# SCH_Claysight-MK1.net
KiCad netlist of a schematic drawn in EasyEDA
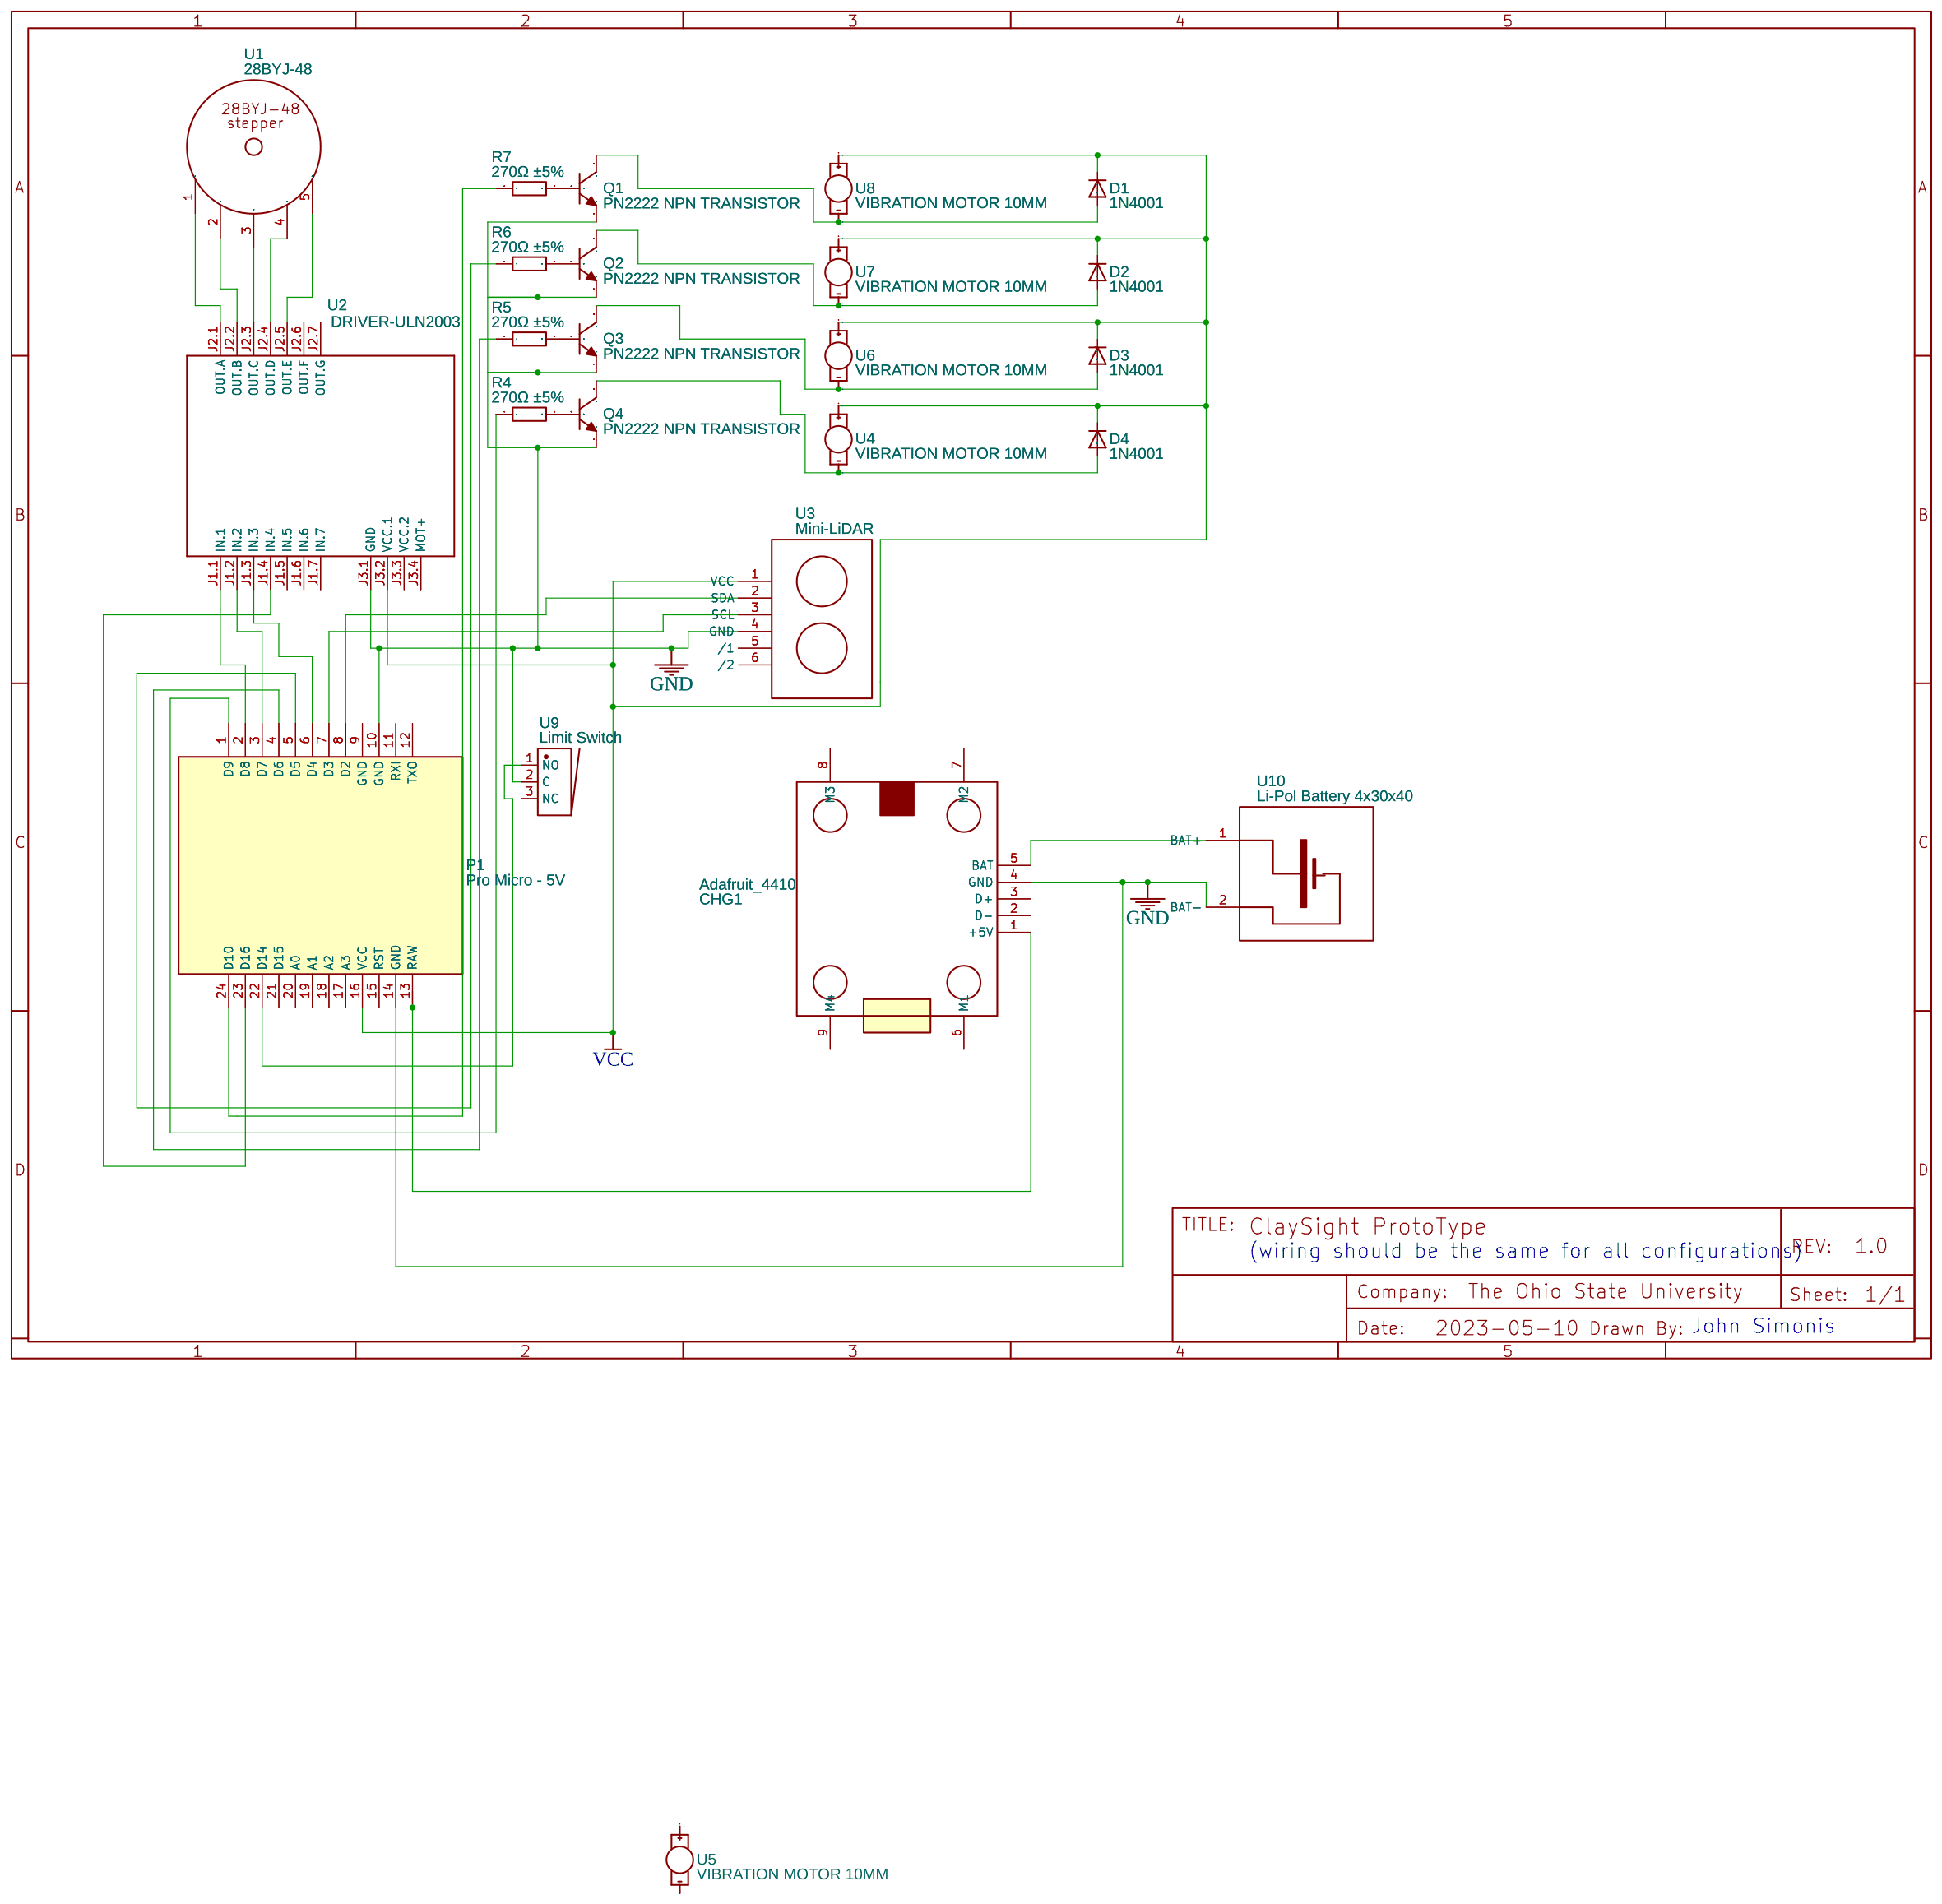
[diagram p0: schematic sheet]

(export (version "E")
  (design (tool "Eeschema 10.0.6"))
  (components
    (comp (ref "CHG1")
      (value "Adafruit_4410")
      (fields (field (name "BOM_Manufacturer Part") "4410") (field (name "BOM_Supplier Part") "1528-4410-ND"))
      (libsource (lib "") (part "Adafruit_4410"))
    )
    (comp (ref "D1") (value "1N4001") (libsource (lib "") (part "1N4001")))
    (comp (ref "D2") (value "1N4001") (libsource (lib "") (part "1N4001")))
    (comp (ref "D3") (value "1N4001") (libsource (lib "") (part "1N4001")))
    (comp (ref "D4") (value "1N4001") (libsource (lib "") (part "1N4001")))
    (comp (ref "P1") (value "Pro Micro - 5V") (libsource (lib "") (part "Pro Micro - 5V")))
    (comp (ref "Q1")
      (value "PN2222 NPN TRANSISTOR")
      (fields (field (name "BOM_Manufacturer Part") "2N3904") (field (name "BOM_Supplier Part") "C713605"))
      (libsource (lib "") (part "PN2222 NPN TRANSISTOR"))
    )
    (comp (ref "Q2")
      (value "PN2222 NPN TRANSISTOR")
      (fields (field (name "BOM_Manufacturer Part") "2N3904") (field (name "BOM_Supplier Part") "C713605"))
      (libsource (lib "") (part "PN2222 NPN TRANSISTOR"))
    )
    (comp (ref "Q3")
      (value "PN2222 NPN TRANSISTOR")
      (fields (field (name "BOM_Manufacturer Part") "2N3904") (field (name "BOM_Supplier Part") "C713605"))
      (libsource (lib "") (part "PN2222 NPN TRANSISTOR"))
    )
    (comp (ref "Q4")
      (value "PN2222 NPN TRANSISTOR")
      (fields (field (name "BOM_Manufacturer Part") "2N3904") (field (name "BOM_Supplier Part") "C713605"))
      (libsource (lib "") (part "PN2222 NPN TRANSISTOR"))
    )
    (comp (ref "R4")
      (value "270Ω ±5%")
      (fields
        (field (name "BOM_Manufacturer Part") "270Ω ±5% 20W")
        (field (name "BOM_Supplier Part") "undefined")
      )
      (libsource (lib "") (part "270Ω ±5% 20W"))
    )
    (comp (ref "R5")
      (value "270Ω ±5%")
      (fields
        (field (name "BOM_Manufacturer Part") "270Ω ±5% 20W")
        (field (name "BOM_Supplier Part") "undefined")
      )
      (libsource (lib "") (part "270Ω ±5% 20W"))
    )
    (comp (ref "R6")
      (value "270Ω ±5%")
      (fields
        (field (name "BOM_Manufacturer Part") "270Ω ±5% 20W")
        (field (name "BOM_Supplier Part") "undefined")
      )
      (libsource (lib "") (part "270Ω ±5% 20W"))
    )
    (comp (ref "R7")
      (value "270Ω ±5%")
      (fields
        (field (name "BOM_Manufacturer Part") "270Ω ±5% 20W")
        (field (name "BOM_Supplier Part") "undefined")
      )
      (libsource (lib "") (part "270Ω ±5% 20W"))
    )
    (comp (ref "U1") (value "28BYJ-48") (libsource (lib "") (part "28BYJ-48")))
    (comp (ref "U2") (value "DRIVER-ULN2003") (libsource (lib "") (part "DRIVER-ULN2003")))
    (comp (ref "U3") (value "Mini-LiDAR") (libsource (lib "") (part "TF Luna LiDAR")))
    (comp (ref "U4") (value "VIBRATION MOTOR 10MM") (libsource (lib "") (part "VIBRATION MOTOR 10MM")))
    (comp (ref "U5") (value "VIBRATION MOTOR 10MM") (libsource (lib "") (part "VIBRATION MOTOR 10MM")))
    (comp (ref "U6") (value "VIBRATION MOTOR 10MM") (libsource (lib "") (part "VIBRATION MOTOR 10MM")))
    (comp (ref "U7") (value "VIBRATION MOTOR 10MM") (libsource (lib "") (part "VIBRATION MOTOR 10MM")))
    (comp (ref "U8") (value "VIBRATION MOTOR 10MM") (libsource (lib "") (part "VIBRATION MOTOR 10MM")))
    (comp (ref "U9") (value "Limit Switch") (libsource (lib "") (part "Limit Switch")))
    (comp (ref "U10")
      (value "Li-Pol Battery 4x30x40")
      (fields (field (name "BOM_Manufacturer Part") "540-563"))
      (libsource (lib "") (part "Li-Pol Battery 4x30x40"))
    )
  )
  (nets
    (net (code "1") (name "GND") (class "Default")
      (node (ref "CHG1") (pin "4") (pinfunction "GND_4") (pintype "unspecified"))
      (node (ref "P1") (pin "10") (pinfunction "GND_10") (pintype "unspecified"))
      (node (ref "P1") (pin "14") (pinfunction "GND_14") (pintype "unspecified"))
      (node (ref "Q1") (pin "1") (pinfunction "E_1") (pintype "unspecified"))
      (node (ref "Q2") (pin "1") (pinfunction "E_1") (pintype "unspecified"))
      (node (ref "Q3") (pin "1") (pinfunction "E_1") (pintype "unspecified"))
      (node (ref "Q4") (pin "1") (pinfunction "E_1") (pintype "unspecified"))
      (node (ref "U2") (pin "J3.1") (pinfunction "GND_J3.1") (pintype "passive"))
      (node (ref "U9") (pin "2") (pinfunction "C_2") (pintype "unspecified"))
    )
    (net (code "2") (name "Net-(CHG1-+5V)") (class "Default")
      (node (ref "CHG1") (pin "1") (pinfunction "+5V_1") (pintype "unspecified"))
      (node (ref "P1") (pin "13") (pinfunction "RAW_13") (pintype "unspecified"))
    )
    (net (code "3") (name "Net-(P1-D4)") (class "Default")
      (node (ref "P1") (pin "6") (pinfunction "D4_6") (pintype "unspecified"))
      (node (ref "U2") (pin "J1.3") (pinfunction "IN.3_J1.3") (pintype "unspecified"))
    )
    (net (code "4") (name "Net-(P1-D5)") (class "Default")
      (node (ref "P1") (pin "5") (pinfunction "D5_5") (pintype "unspecified"))
      (node (ref "R6") (pin "1") (pinfunction "1_1") (pintype "input"))
    )
    (net (code "5") (name "Net-(P1-D6)") (class "Default")
      (node (ref "P1") (pin "4") (pinfunction "D6_4") (pintype "unspecified"))
      (node (ref "R5") (pin "1") (pinfunction "1_1") (pintype "input"))
    )
    (net (code "6") (name "Net-(P1-D7)") (class "Default")
      (node (ref "P1") (pin "3") (pinfunction "D7_3") (pintype "unspecified"))
      (node (ref "U2") (pin "J1.2") (pinfunction "IN.2_J1.2") (pintype "unspecified"))
    )
    (net (code "7") (name "Net-(P1-D8)") (class "Default")
      (node (ref "P1") (pin "2") (pinfunction "D8_2") (pintype "unspecified"))
      (node (ref "U2") (pin "J1.1") (pinfunction "IN.1_J1.1") (pintype "unspecified"))
    )
    (net (code "8") (name "Net-(P1-D9)") (class "Default")
      (node (ref "P1") (pin "1") (pinfunction "D9_1") (pintype "unspecified"))
      (node (ref "R4") (pin "1") (pinfunction "1_1") (pintype "input"))
    )
    (net (code "9") (name "Net-(P1-D10)") (class "Default")
      (node (ref "P1") (pin "24") (pinfunction "D10_24") (pintype "unspecified"))
      (node (ref "R7") (pin "1") (pinfunction "1_1") (pintype "input"))
    )
    (net (code "10") (name "Net-(P1-D14)") (class "Default")
      (node (ref "P1") (pin "22") (pinfunction "D14_22") (pintype "unspecified"))
      (node (ref "U9") (pin "1") (pinfunction "NO_1") (pintype "unspecified"))
    )
    (net (code "11") (name "Net-(P1-D16)") (class "Default")
      (node (ref "P1") (pin "23") (pinfunction "D16_23") (pintype "unspecified"))
      (node (ref "U2") (pin "J1.4") (pinfunction "IN.4_J1.4") (pintype "unspecified"))
    )
    (net (code "12") (name "Net-(Q1-B)") (class "Default")
      (node (ref "Q1") (pin "2") (pinfunction "B_2") (pintype "unspecified"))
      (node (ref "R7") (pin "2") (pinfunction "2_2") (pintype "input"))
    )
    (net (code "13") (name "Net-(Q1-C)") (class "Default")
      (node (ref "D1") (pin "A") (pinfunction "A_A") (pintype "unspecified"))
      (node (ref "Q1") (pin "3") (pinfunction "C_3") (pintype "unspecified"))
      (node (ref "U8") (pin "-") (pinfunction "-_-") (pintype "unspecified"))
    )
    (net (code "14") (name "Net-(Q2-B)") (class "Default")
      (node (ref "Q2") (pin "2") (pinfunction "B_2") (pintype "unspecified"))
      (node (ref "R6") (pin "2") (pinfunction "2_2") (pintype "input"))
    )
    (net (code "15") (name "Net-(Q2-C)") (class "Default")
      (node (ref "D2") (pin "A") (pinfunction "A_A") (pintype "unspecified"))
      (node (ref "Q2") (pin "3") (pinfunction "C_3") (pintype "unspecified"))
      (node (ref "U7") (pin "-") (pinfunction "-_-") (pintype "unspecified"))
    )
    (net (code "16") (name "Net-(Q3-B)") (class "Default")
      (node (ref "Q3") (pin "2") (pinfunction "B_2") (pintype "unspecified"))
      (node (ref "R5") (pin "2") (pinfunction "2_2") (pintype "input"))
    )
    (net (code "17") (name "Net-(Q3-C)") (class "Default")
      (node (ref "D3") (pin "A") (pinfunction "A_A") (pintype "unspecified"))
      (node (ref "Q3") (pin "3") (pinfunction "C_3") (pintype "unspecified"))
      (node (ref "U6") (pin "-") (pinfunction "-_-") (pintype "unspecified"))
    )
    (net (code "18") (name "Net-(Q4-B)") (class "Default")
      (node (ref "Q4") (pin "2") (pinfunction "B_2") (pintype "unspecified"))
      (node (ref "R4") (pin "2") (pinfunction "2_2") (pintype "input"))
    )
    (net (code "19") (name "Net-(Q4-C)") (class "Default")
      (node (ref "D4") (pin "A") (pinfunction "A_A") (pintype "unspecified"))
      (node (ref "Q4") (pin "3") (pinfunction "C_3") (pintype "unspecified"))
      (node (ref "U4") (pin "-") (pinfunction "-_-") (pintype "unspecified"))
    )
    (net (code "20") (name "Net-(U2-OUT.A)") (class "Default")
      (node (ref "U1") (pin "1") (pinfunction "1_1") (pintype "unspecified"))
      (node (ref "U2") (pin "J2.1") (pinfunction "OUT.A_J2.1") (pintype "unspecified"))
    )
    (net (code "21") (name "Net-(U2-OUT.B)") (class "Default")
      (node (ref "U1") (pin "2") (pinfunction "2_2") (pintype "unspecified"))
      (node (ref "U2") (pin "J2.2") (pinfunction "OUT.B_J2.2") (pintype "unspecified"))
    )
    (net (code "22") (name "Net-(U2-OUT.C)") (class "Default")
      (node (ref "U1") (pin "3") (pinfunction "3_3") (pintype "unspecified"))
      (node (ref "U2") (pin "J2.3") (pinfunction "OUT.C_J2.3") (pintype "unspecified"))
    )
    (net (code "23") (name "Net-(U2-OUT.D)") (class "Default")
      (node (ref "U1") (pin "4") (pinfunction "4_4") (pintype "unspecified"))
      (node (ref "U2") (pin "J2.4") (pinfunction "OUT.D_J2.4") (pintype "unspecified"))
    )
    (net (code "24") (name "Net-(U2-OUT.E)") (class "Default")
      (node (ref "U1") (pin "5") (pinfunction "5_5") (pintype "unspecified"))
      (node (ref "U2") (pin "J2.5") (pinfunction "OUT.E_J2.5") (pintype "unspecified"))
    )
    (net (code "25") (name "VCC") (class "Default")
      (node (ref "D1") (pin "C") (pinfunction "C_C") (pintype "unspecified"))
      (node (ref "D2") (pin "C") (pinfunction "C_C") (pintype "unspecified"))
      (node (ref "D3") (pin "C") (pinfunction "C_C") (pintype "unspecified"))
      (node (ref "D4") (pin "C") (pinfunction "C_C") (pintype "unspecified"))
      (node (ref "P1") (pin "16") (pinfunction "VCC_16") (pintype "unspecified"))
      (node (ref "U2") (pin "J3.2") (pinfunction "VCC.1_J3.2") (pintype "passive"))
      (node (ref "U4") (pin "+") (pinfunction "+_+") (pintype "unspecified"))
      (node (ref "U6") (pin "+") (pinfunction "+_+") (pintype "unspecified"))
      (node (ref "U7") (pin "+") (pinfunction "+_+") (pintype "unspecified"))
      (node (ref "U8") (pin "+") (pinfunction "+_+") (pintype "unspecified"))
    )
    (net (code "26") (name "unconnected-(CHG1-BAT-Pad5)") (class "Default")
      (node (ref "CHG1") (pin "5") (pinfunction "BAT_5") (pintype "unspecified"))
    )
    (net (code "27") (name "unconnected-(CHG1-D+-Pad3)") (class "Default")
      (node (ref "CHG1") (pin "3") (pinfunction "D+_3") (pintype "unspecified"))
    )
    (net (code "28") (name "unconnected-(CHG1-D--Pad2)") (class "Default")
      (node (ref "CHG1") (pin "2") (pinfunction "D-_2") (pintype "unspecified"))
    )
    (net (code "29") (name "unconnected-(CHG1-M1-Pad6)") (class "Default")
      (node (ref "CHG1") (pin "6") (pinfunction "M1_6") (pintype "unspecified"))
    )
    (net (code "30") (name "unconnected-(CHG1-M2-Pad7)") (class "Default")
      (node (ref "CHG1") (pin "7") (pinfunction "M2_7") (pintype "unspecified"))
    )
    (net (code "31") (name "unconnected-(CHG1-M3-Pad8)") (class "Default")
      (node (ref "CHG1") (pin "8") (pinfunction "M3_8") (pintype "unspecified"))
    )
    (net (code "32") (name "unconnected-(CHG1-M4-Pad9)") (class "Default")
      (node (ref "CHG1") (pin "9") (pinfunction "M4_9") (pintype "unspecified"))
    )
    (net (code "33") (name "unconnected-(P1-A0-Pad20)") (class "Default")
      (node (ref "P1") (pin "20") (pinfunction "A0_20") (pintype "unspecified"))
    )
    (net (code "34") (name "unconnected-(P1-A1-Pad19)") (class "Default")
      (node (ref "P1") (pin "19") (pinfunction "A1_19") (pintype "unspecified"))
    )
    (net (code "35") (name "unconnected-(P1-A2-Pad18)") (class "Default")
      (node (ref "P1") (pin "18") (pinfunction "A2_18") (pintype "unspecified"))
    )
    (net (code "36") (name "unconnected-(P1-A3-Pad17)") (class "Default")
      (node (ref "P1") (pin "17") (pinfunction "A3_17") (pintype "unspecified"))
    )
    (net (code "37") (name "unconnected-(P1-D2-Pad8)") (class "Default")
      (node (ref "P1") (pin "8") (pinfunction "D2_8") (pintype "unspecified"))
    )
    (net (code "38") (name "unconnected-(P1-D3-Pad7)") (class "Default")
      (node (ref "P1") (pin "7") (pinfunction "D3_7") (pintype "unspecified"))
    )
    (net (code "39") (name "unconnected-(P1-D15-Pad21)") (class "Default")
      (node (ref "P1") (pin "21") (pinfunction "D15_21") (pintype "unspecified"))
    )
    (net (code "40") (name "unconnected-(P1-GND-Pad9)") (class "Default")
      (node (ref "P1") (pin "9") (pinfunction "GND_9") (pintype "unspecified"))
    )
    (net (code "41") (name "unconnected-(P1-RST-Pad15)") (class "Default")
      (node (ref "P1") (pin "15") (pinfunction "RST_15") (pintype "unspecified"))
    )
    (net (code "42") (name "unconnected-(P1-RXI-Pad11)") (class "Default")
      (node (ref "P1") (pin "11") (pinfunction "RXI_11") (pintype "unspecified"))
    )
    (net (code "43") (name "unconnected-(P1-TXO-Pad12)") (class "Default")
      (node (ref "P1") (pin "12") (pinfunction "TXO_12") (pintype "unspecified"))
    )
    (net (code "44") (name "unconnected-(U2-IN.5-PadJ1.5)") (class "Default")
      (node (ref "U2") (pin "J1.5") (pinfunction "IN.5_J1.5") (pintype "unspecified"))
    )
    (net (code "45") (name "unconnected-(U2-IN.6-PadJ1.6)") (class "Default")
      (node (ref "U2") (pin "J1.6") (pinfunction "IN.6_J1.6") (pintype "unspecified"))
    )
    (net (code "46") (name "unconnected-(U2-IN.7-PadJ1.7)") (class "Default")
      (node (ref "U2") (pin "J1.7") (pinfunction "IN.7_J1.7") (pintype "unspecified"))
    )
    (net (code "47") (name "unconnected-(U2-MOT+-PadJ3.4)") (class "Default")
      (node (ref "U2") (pin "J3.4") (pinfunction "MOT+_J3.4") (pintype "unspecified"))
    )
    (net (code "48") (name "unconnected-(U2-OUT.F-PadJ2.6)") (class "Default")
      (node (ref "U2") (pin "J2.6") (pinfunction "OUT.F_J2.6") (pintype "unspecified"))
    )
    (net (code "49") (name "unconnected-(U2-OUT.G-PadJ2.7)") (class "Default")
      (node (ref "U2") (pin "J2.7") (pinfunction "OUT.G_J2.7") (pintype "unspecified"))
    )
    (net (code "50") (name "unconnected-(U2-VCC.2-PadJ3.3)") (class "Default")
      (node (ref "U2") (pin "J3.3") (pinfunction "VCC.2_J3.3") (pintype "unspecified"))
    )
    (net (code "51") (name "unconnected-(U3-GND-Pad4)") (class "Default")
      (node (ref "U3") (pin "4") (pinfunction "GND_4") (pintype "unspecified"))
    )
    (net (code "52") (name "unconnected-(U3-SCL-Pad3)") (class "Default")
      (node (ref "U3") (pin "3") (pinfunction "SCL_3") (pintype "unspecified"))
    )
    (net (code "53") (name "unconnected-(U3-SDA-Pad2)") (class "Default")
      (node (ref "U3") (pin "2") (pinfunction "SDA_2") (pintype "unspecified"))
    )
    (net (code "54") (name "unconnected-(U3-VCC-Pad1)") (class "Default")
      (node (ref "U3") (pin "1") (pinfunction "VCC_1") (pintype "unspecified"))
    )
    (net (code "55") (name "unconnected-(U3-{slash}1-Pad5)") (class "Default")
      (node (ref "U3") (pin "5") (pinfunction "/1_5") (pintype "unspecified"))
    )
    (net (code "56") (name "unconnected-(U3-{slash}2-Pad6)") (class "Default")
      (node (ref "U3") (pin "6") (pinfunction "/2_6") (pintype "unspecified"))
    )
    (net (code "57") (name "unconnected-(U5-Pad+)") (class "Default")
      (node (ref "U5") (pin "+") (pinfunction "+_+") (pintype "unspecified"))
    )
    (net (code "58") (name "unconnected-(U5-Pad-)") (class "Default")
      (node (ref "U5") (pin "-") (pinfunction "-_-") (pintype "unspecified"))
    )
    (net (code "59") (name "unconnected-(U9-NC-Pad3)") (class "Default")
      (node (ref "U9") (pin "3") (pinfunction "NC_3") (pintype "unspecified"))
    )
    (net (code "60") (name "unconnected-(U10-BAT+-Pad1)") (class "Default")
      (node (ref "U10") (pin "1") (pinfunction "BAT+_1") (pintype "unspecified"))
    )
    (net (code "61") (name "unconnected-(U10-BAT--Pad2)") (class "Default")
      (node (ref "U10") (pin "2") (pinfunction "BAT-_2") (pintype "unspecified"))
    )
  )
)
